# BSPD.net
KiCad netlist of a schematic drawn in Altium Designer
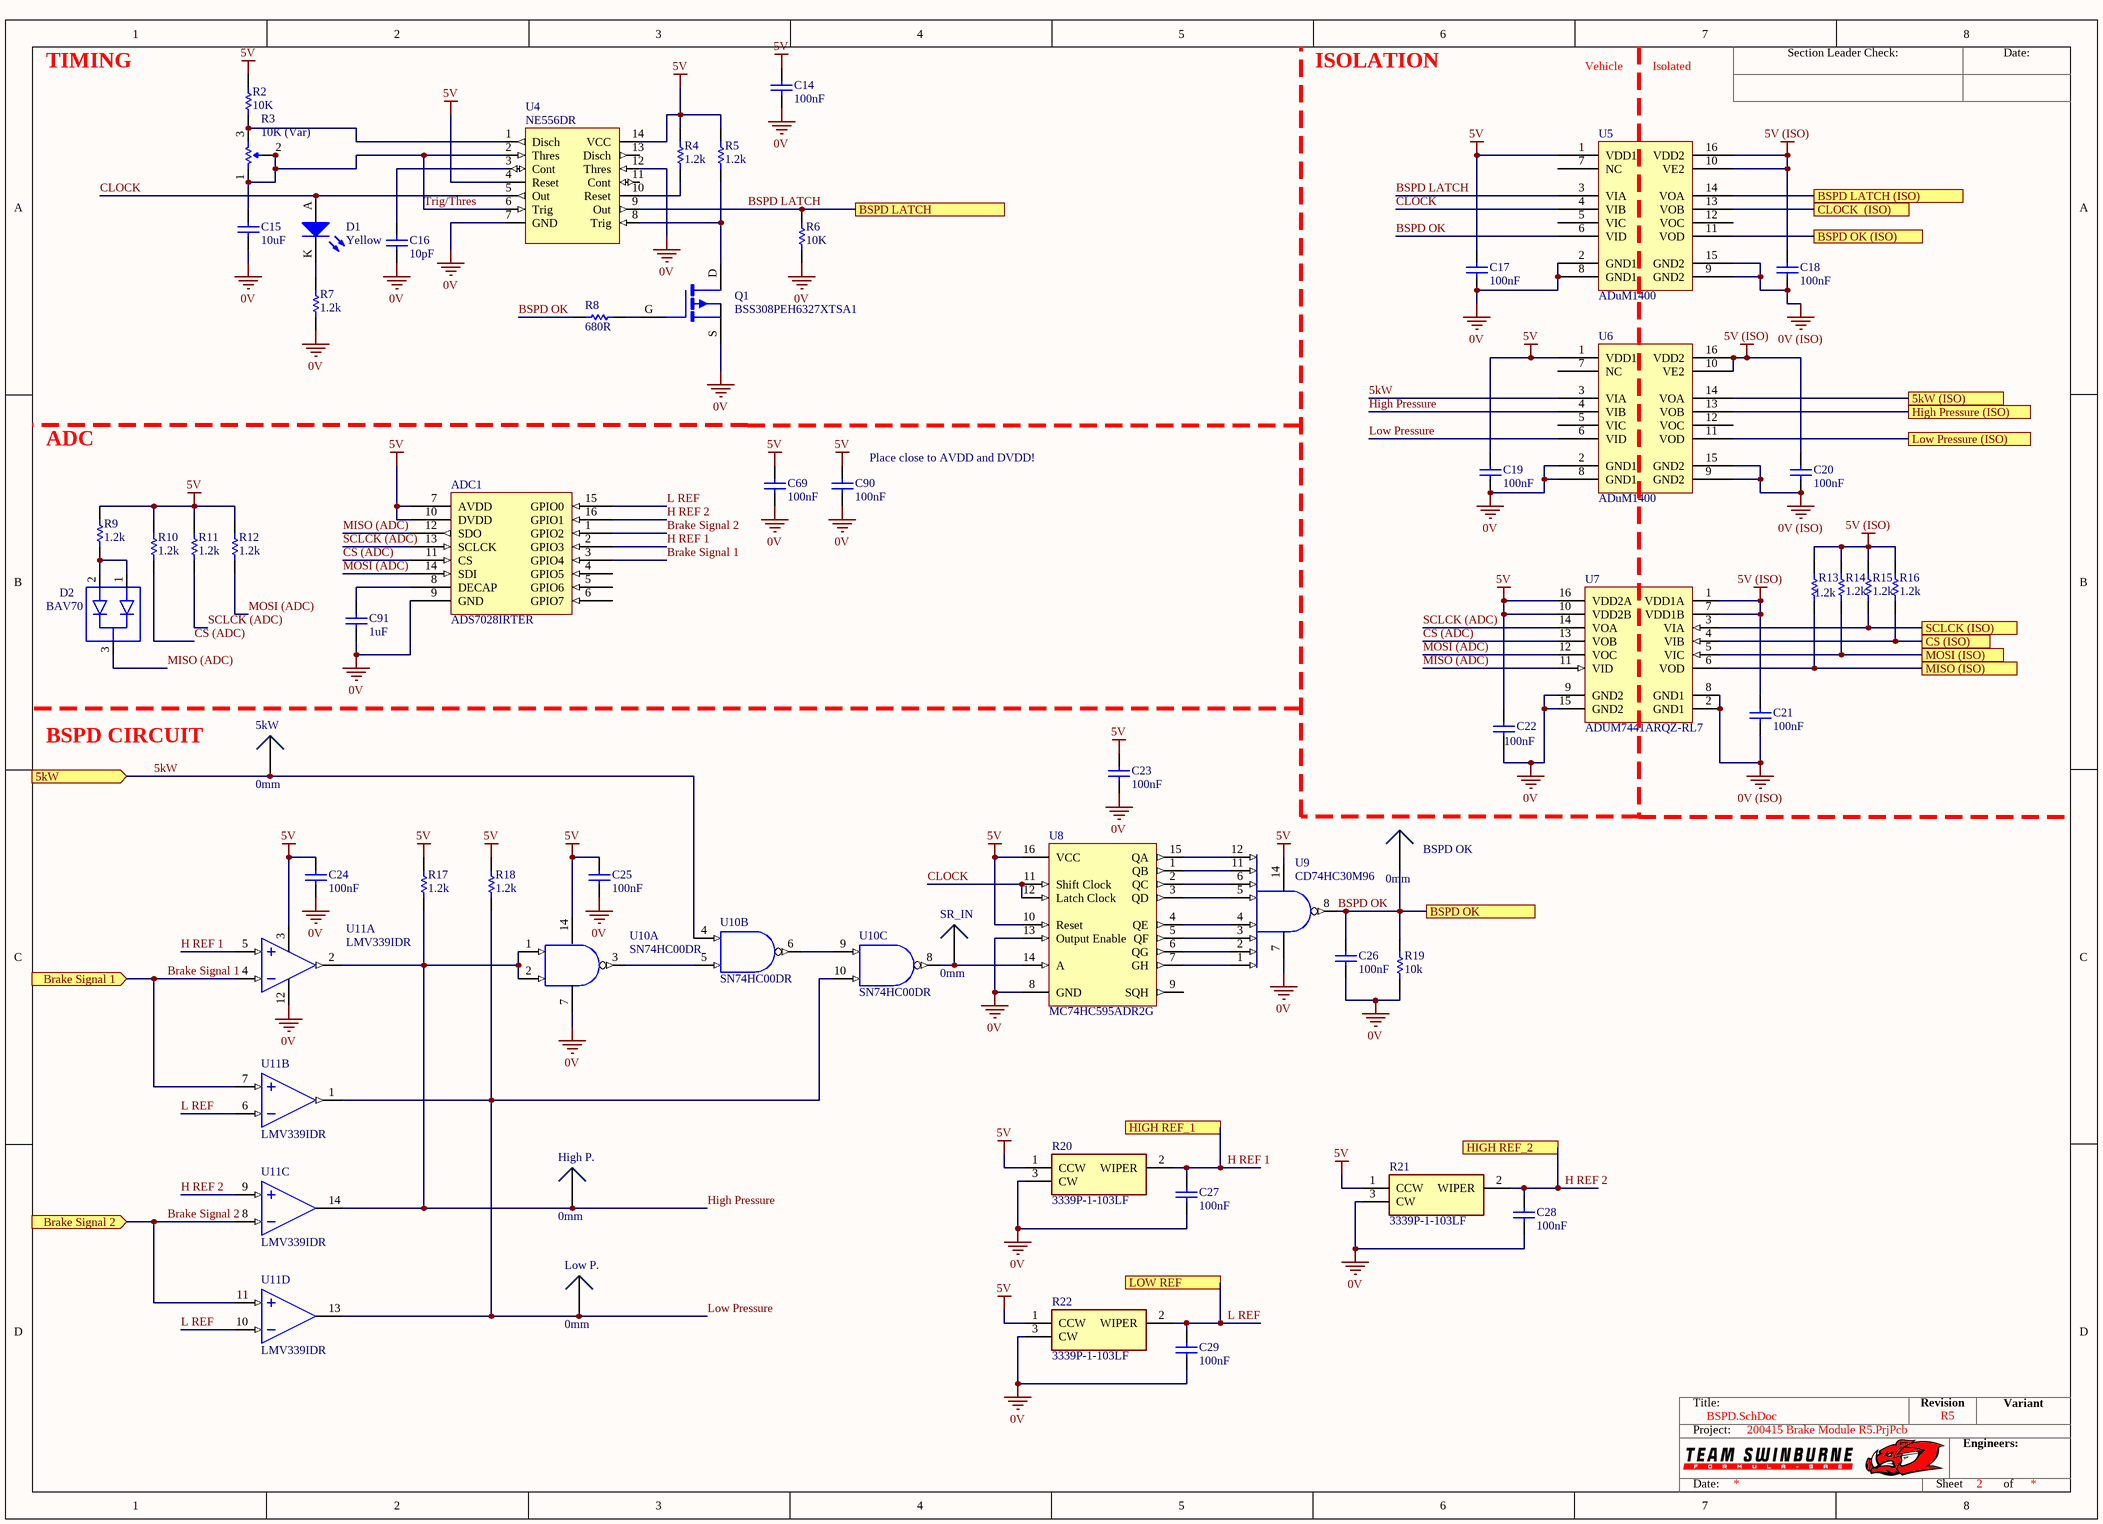
[diagram p0: BSPD.SchDoc]

(export (version "E")
  (design (tool "Eeschema 10.0.6"))
  (components
    (comp (ref "5kW")
      (value "0mm")
      (footprint "SMD Test Point")
      (fields (field (name "PART NUMBER") "SMD Test Point") (field (name "CONTACT") "NA"))
      (libsource (lib "ts_20-standard-connectors") (part "Test Point"))
    )
    (comp (ref "ADC1")
      (value "ADS7028IRTER")
      (footprint "WFQN-16")
      (description "IC ADC 12BIT SAR 16WQFN")
      (fields (field (name "MANUFACTURER") "Texas Instruments"))
      (libsource (lib "ts_standard_library") (part "ADS7028IRTER"))
    )
    (comp (ref "BSPD OK")
      (value "0mm")
      (footprint "SMD Test Point")
      (fields (field (name "PART NUMBER") "SMD Test Point") (field (name "CONTACT") "NA"))
      (libsource (lib "ts_20-standard-connectors") (part "Test Point"))
    )
    (comp (ref "C14")
      (value "100nF")
      (footprint "C0603")
      (fields (field (name "PART NUMBER") "CC0603ZPY5V9BB104") (field (name "TOLERANCE") "5%"))
      (libsource (lib "AMS_Component_Library") (part "Capacitor"))
    )
    (comp (ref "C15")
      (value "10uF")
      (footprint "C0603")
      (fields (field (name "PART NUMBER") "GRM188R6YA106MA73D") (field (name "TOLERANCE") "20%"))
      (libsource (lib "AMS_Component_Library") (part "Capacitor"))
    )
    (comp (ref "C16")
      (value "10pF")
      (footprint "C0603")
      (fields (field (name "PART NUMBER") "CC0603JPNPO9BN100") (field (name "TOLERANCE") "5%"))
      (libsource (lib "AMS_Component_Library") (part "Capacitor"))
    )
    (comp (ref "C17")
      (value "100nF")
      (footprint "C0603")
      (fields (field (name "PART NUMBER") "CC0603ZPY5V9BB104") (field (name "TOLERANCE") "5%"))
      (libsource (lib "AMS_Component_Library") (part "Capacitor"))
    )
    (comp (ref "C18")
      (value "100nF")
      (footprint "C0603")
      (fields (field (name "PART NUMBER") "CC0603ZPY5V9BB104") (field (name "TOLERANCE") "5%"))
      (libsource (lib "AMS_Component_Library") (part "Capacitor"))
    )
    (comp (ref "C19")
      (value "100nF")
      (footprint "C0603")
      (fields (field (name "PART NUMBER") "CC0603ZPY5V9BB104") (field (name "TOLERANCE") "5%"))
      (libsource (lib "AMS_Component_Library") (part "Capacitor"))
    )
    (comp (ref "C20")
      (value "100nF")
      (footprint "C0603")
      (fields (field (name "PART NUMBER") "CC0603ZPY5V9BB104") (field (name "TOLERANCE") "5%"))
      (libsource (lib "AMS_Component_Library") (part "Capacitor"))
    )
    (comp (ref "C21")
      (value "100nF")
      (footprint "C0603")
      (fields (field (name "PART NUMBER") "CC0603ZPY5V9BB104") (field (name "TOLERANCE") "5%"))
      (libsource (lib "AMS_Component_Library") (part "Capacitor"))
    )
    (comp (ref "C22")
      (value "100nF")
      (footprint "C0603")
      (fields (field (name "PART NUMBER") "CC0603ZPY5V9BB104") (field (name "TOLERANCE") "5%"))
      (libsource (lib "AMS_Component_Library") (part "Capacitor"))
    )
    (comp (ref "C23")
      (value "100nF")
      (footprint "C0603")
      (fields (field (name "PART NUMBER") "CC0603ZPY5V9BB104") (field (name "TOLERANCE") "5%"))
      (libsource (lib "AMS_Component_Library") (part "Capacitor"))
    )
    (comp (ref "C24")
      (value "100nF")
      (footprint "C0603")
      (fields (field (name "PART NUMBER") "CC0603ZPY5V9BB104") (field (name "TOLERANCE") "5%"))
      (libsource (lib "AMS_Component_Library") (part "Capacitor"))
    )
    (comp (ref "C25")
      (value "100nF")
      (footprint "C0603")
      (fields (field (name "PART NUMBER") "CC0603ZPY5V9BB104") (field (name "TOLERANCE") "5%"))
      (libsource (lib "AMS_Component_Library") (part "Capacitor"))
    )
    (comp (ref "C26")
      (value "100nF")
      (footprint "C0603")
      (fields (field (name "PART NUMBER") "CC0603ZPY5V9BB104") (field (name "TOLERANCE") "5%"))
      (libsource (lib "AMS_Component_Library") (part "Capacitor"))
    )
    (comp (ref "C27")
      (value "100nF")
      (footprint "0805")
      (fields
        (field (name "PART NUMBER") "GCM21BR71H104KA37L")
        (field (name "TOLERANCE") "±10%")
        (field (name "MANUFACTURER") "muRata")
      )
      (libsource (lib "ts_20-standard-library") (part "Capacitor"))
    )
    (comp (ref "C28")
      (value "100nF")
      (footprint "0805")
      (fields
        (field (name "PART NUMBER") "GCM21BR71H104KA37L")
        (field (name "TOLERANCE") "±10%")
        (field (name "MANUFACTURER") "muRata")
      )
      (libsource (lib "ts_20-standard-library") (part "Capacitor"))
    )
    (comp (ref "C29")
      (value "100nF")
      (footprint "0805")
      (fields
        (field (name "PART NUMBER") "GCM21BR71H104KA37L")
        (field (name "TOLERANCE") "±10%")
        (field (name "MANUFACTURER") "muRata")
      )
      (libsource (lib "ts_20-standard-library") (part "Capacitor"))
    )
    (comp (ref "C69")
      (value "100nF")
      (footprint "C0603")
      (fields (field (name "PART NUMBER") "CC0603ZPY5V9BB104") (field (name "TOLERANCE") "5%"))
      (libsource (lib "AMS_Component_Library") (part "Capacitor"))
    )
    (comp (ref "C90")
      (value "100nF")
      (footprint "C0603")
      (fields (field (name "PART NUMBER") "CC0603ZPY5V9BB104") (field (name "TOLERANCE") "5%"))
      (libsource (lib "AMS_Component_Library") (part "Capacitor"))
    )
    (comp (ref "C91")
      (value "1uF")
      (footprint "0603")
      (fields
        (field (name "PART NUMBER") "GRT188R61H105ME13D")
        (field (name "TOLERANCE") "20%")
        (field (name "MANUFACTURER") "muRata")
      )
      (libsource (lib "ts_20-standard-library") (part "Capacitor"))
    )
    (comp (ref "D1")
      (value "Yellow")
      (footprint "0805 LED")
      (description "Yellow LED Indication - Discrete 1.75V 0805 (2012 Metric)")
      (fields (field (name "PART NUMBER") "SML-211YTT86") (field (name "MANUFACTURER") "ROHM Semiconductor"))
      (libsource (lib "ts_20-standard-library") (part "LED"))
    )
    (comp (ref "D2")
      (value "BAV70")
      (footprint "BAV70-Footprint-1")
      (description "DIODE ARRAY GP 70V 200mA SOT23-3")
      (libsource (lib "Team Swinburne") (part "BAV70-Symbol-1"))
    )
    (comp (ref "High P.")
      (value "0mm")
      (footprint "SMD Test Point")
      (fields (field (name "PART NUMBER") "SMD Test Point") (field (name "CONTACT") "NA"))
      (libsource (lib "ts_20-standard-connectors") (part "Test Point"))
    )
    (comp (ref "Low P.")
      (value "0mm")
      (footprint "SMD Test Point")
      (fields (field (name "PART NUMBER") "SMD Test Point") (field (name "CONTACT") "NA"))
      (libsource (lib "ts_20-standard-connectors") (part "Test Point"))
    )
    (comp (ref "Q1")
      (value "BSS308PEH6327XTSA1")
      (footprint "IN SOT-23 MOSFET")
      (description "P-Channel 30V 2A (Ta) 500mW (Ta) Surface Mount SOT-23-3")
      (fields
        (field (name "MANUFACTURER") "Infineon Technologies")
        (field (name "DIGIKEY PART NUMBER") "BSS308PEH6327XTSA1CT-ND")
        (field (name "PUBLISHER") "Altium Limited")
      )
      (libsource (lib "ts_20-standard-library") (part "MOSFET-P"))
    )
    (comp (ref "R2")
      (value "10K")
      (footprint "R0603")
      (fields (field (name "PART NUMBER") "RA73F1J10KBTD") (field (name "TOLERANCE") "0.1%"))
      (libsource (lib "AMS_Component_Library") (part "Resistor"))
    )
    (comp (ref "R3")
      (value "10K (Var)")
      (footprint "B 3296")
      (fields
        (field (name "PART NUMBER") "3296W-1-103LF")
        (field (name "MANUFACTURER") "Bournes Inc")
        (field (name "TOLERANCE") "0.1")
      )
      (libsource (lib "ts_20-standard-library") (part "Resistor (Potentiometer)"))
    )
    (comp (ref "R4")
      (value "1.2k")
      (footprint "R0603")
      (fields (field (name "PART NUMBER") "ERJ-PA3J122V") (field (name "TOLERANCE") "1%"))
      (libsource (lib "AMS_Component_Library") (part "Resistor"))
    )
    (comp (ref "R5")
      (value "1.2k")
      (footprint "R0603")
      (fields (field (name "PART NUMBER") "ERJ-PA3J122V") (field (name "TOLERANCE") "1%"))
      (libsource (lib "AMS_Component_Library") (part "Resistor"))
    )
    (comp (ref "R6")
      (value "10K")
      (footprint "R0603")
      (fields (field (name "PART NUMBER") "RA73F1J10KBTD") (field (name "TOLERANCE") "0.1%"))
      (libsource (lib "AMS_Component_Library") (part "Resistor"))
    )
    (comp (ref "R7")
      (value "1.2k")
      (footprint "R0603")
      (fields (field (name "PART NUMBER") "ERJ-PA3J122V") (field (name "TOLERANCE") "1%"))
      (libsource (lib "AMS_Component_Library") (part "Resistor"))
    )
    (comp (ref "R8")
      (value "680R")
      (footprint "R0603")
      (fields (field (name "PART NUMBER") "RCP0603B680RGEA") (field (name "TOLERANCE") "2%"))
      (libsource (lib "AMS_Component_Library") (part "Resistor"))
    )
    (comp (ref "R9")
      (value "1.2k")
      (footprint "R0603")
      (fields (field (name "PART NUMBER") "ERJ-PA3J122V") (field (name "TOLERANCE") "1%"))
      (libsource (lib "AMS_Component_Library") (part "Resistor"))
    )
    (comp (ref "R10")
      (value "1.2k")
      (footprint "R0603")
      (fields (field (name "PART NUMBER") "ERJ-PA3J122V") (field (name "TOLERANCE") "1%"))
      (libsource (lib "AMS_Component_Library") (part "Resistor"))
    )
    (comp (ref "R11")
      (value "1.2k")
      (footprint "R0603")
      (fields (field (name "PART NUMBER") "ERJ-PA3J122V") (field (name "TOLERANCE") "1%"))
      (libsource (lib "AMS_Component_Library") (part "Resistor"))
    )
    (comp (ref "R12")
      (value "1.2k")
      (footprint "R0603")
      (fields (field (name "PART NUMBER") "ERJ-PA3J122V") (field (name "TOLERANCE") "1%"))
      (libsource (lib "AMS_Component_Library") (part "Resistor"))
    )
    (comp (ref "R13")
      (value "1.2k")
      (footprint "R0603")
      (fields (field (name "PART NUMBER") "ERJ-PA3J122V") (field (name "TOLERANCE") "1%"))
      (libsource (lib "AMS_Component_Library") (part "Resistor"))
    )
    (comp (ref "R14")
      (value "1.2k")
      (footprint "R0603")
      (fields (field (name "PART NUMBER") "ERJ-PA3J122V") (field (name "TOLERANCE") "1%"))
      (libsource (lib "AMS_Component_Library") (part "Resistor"))
    )
    (comp (ref "R15")
      (value "1.2k")
      (footprint "R0603")
      (fields (field (name "PART NUMBER") "ERJ-PA3J122V") (field (name "TOLERANCE") "1%"))
      (libsource (lib "AMS_Component_Library") (part "Resistor"))
    )
    (comp (ref "R16")
      (value "1.2k")
      (footprint "R0603")
      (fields (field (name "PART NUMBER") "ERJ-PA3J122V") (field (name "TOLERANCE") "1%"))
      (libsource (lib "AMS_Component_Library") (part "Resistor"))
    )
    (comp (ref "R17")
      (value "1.2k")
      (footprint "R0603")
      (fields (field (name "PART NUMBER") "ERJ-PA3J122V") (field (name "TOLERANCE") "1%"))
      (libsource (lib "AMS_Component_Library") (part "Resistor"))
    )
    (comp (ref "R18")
      (value "1.2k")
      (footprint "R0603")
      (fields (field (name "PART NUMBER") "ERJ-PA3J122V") (field (name "TOLERANCE") "1%"))
      (libsource (lib "AMS_Component_Library") (part "Resistor"))
    )
    (comp (ref "R19")
      (value "10k")
      (footprint "0805")
      (fields
        (field (name "PART NUMBER") "RC0805FR0710KL")
        (field (name "MANUFACTURER") "YAGEO")
        (field (name "TOLERANCE") "0.01")
      )
      (libsource (lib "ts_20-standard-library") (part "Resistor"))
    )
    (comp (ref "R20")
      (value "3339P-1-103LF")
      (footprint "SamacSys:3339P1103LF")
      (description "Variable Resistor")
      (fields (field (name "MOUSER PART NUMBER") "652-3339P-1-103LF"))
      (libsource (lib "*") (part "3339P-1-103LF"))
    )
    (comp (ref "R21")
      (value "3339P-1-103LF")
      (footprint "SamacSys:3339P1103LF")
      (description "Variable Resistor")
      (fields (field (name "MOUSER PART NUMBER") "652-3339P-1-103LF"))
      (libsource (lib "*") (part "3339P-1-103LF"))
    )
    (comp (ref "R22")
      (value "3339P-1-103LF")
      (footprint "SamacSys:3339P1103LF")
      (description "Variable Resistor")
      (fields (field (name "MOUSER PART NUMBER") "652-3339P-1-103LF"))
      (libsource (lib "*") (part "3339P-1-103LF"))
    )
    (comp (ref "SR_IN")
      (value "0mm")
      (footprint "SMD Test Point")
      (fields (field (name "PART NUMBER") "SMD Test Point") (field (name "CONTACT") "NA"))
      (libsource (lib "ts_20-standard-connectors") (part "Test Point"))
    )
    (comp (ref "U4")
      (value "NE556DR")
      (footprint "14 SOIC")
      (description "IC OSC TIMER DUAL 100KHZ 14SOIC")
      (fields
        (field (name "MANUFACTURER") "Texas Instruments")
        (field (name "DIGIKEY PART NUMBER") "296-26240-1-ND")
      )
      (libsource (lib "ts_20-standard-library") (part "NE556DR"))
    )
    (comp (ref "U5")
      (value "ADuM1400")
      (footprint "SOIC16-W")
      (description "DIGITAL ISOLATOR, QUAD CHANNEL")
      (libsource (lib "AMS_Component_Library") (part "ADuM1400"))
    )
    (comp (ref "U6")
      (value "ADuM1400")
      (footprint "SOIC16-W")
      (description "DIGITAL ISOLATOR, QUAD CHANNEL")
      (libsource (lib "AMS_Component_Library") (part "ADuM1400"))
    )
    (comp (ref "U7")
      (value "ADUM7441ARQZ-RL7")
      (footprint "ADI-RQ-16_M")
      (description "Digital Isolator CMOS 4-CH 1Mbps 16-Pin QSOP T/R")
      (libsource (lib "Team Swinburne") (part "ADI-ADUM7441-RQ-16"))
    )
    (comp (ref "U8")
      (value "MC74HC595ADR2G")
      (footprint "ON 16-SOIC")
      (description "IC SHIFT REGISTR 8BIT 3ST 16SOIC")
      (fields
        (field (name "MANUFACTURER") "ON Semiconductor")
        (field (name "DIGIKEY PART NUMBER") "MC74HC595ADR2GOSCT-ND")
      )
      (libsource (lib "ts_20-standard-library") (part "MC74HC595ADR2G"))
    )
    (comp (ref "U9")
      (value "CD74HC30M96")
      (footprint "TI 14-SOIC")
      (description "IC GATE NAND 1CH 8-INP 14SOIC")
      (fields
        (field (name "MANUFACTURER") "Texas Instruments")
        (field (name "DIGIKEY PART NUMBER") "296-14521-1-ND")
      )
      (libsource (lib "ts_20-standard-library") (part "CD74HC30M96"))
    )
    (comp (ref "U10")
      (value "SN74HC00DR")
      (footprint "TI 14-SOIC")
      (description "NAND Gate IC 4 Channel 14-SOIC")
      (fields
        (field (name "MANUFACTURER") "Texas Instruments")
        (field (name "DIGIKEY PART NUMBER") "296-1187-2-ND")
      )
      (libsource (lib "ts_20-standard-library") (part "SN74HC00DR"))
    )
    (comp (ref "U11")
      (value "LMV339IDR")
      (footprint "TI 14-SOIC")
      (description "Comparator General Purpose Open Collector 14-SOIC")
      (fields
        (field (name "MANUFACTURER") "Texas Instruments")
        (field (name "DIGIKEY PART NUMBER") "296-6611-2-ND")
      )
      (libsource (lib "ts_20-standard-library") (part "LMV339IDR"))
    )
  )
  (nets
    (net (code "1") (name "/5kW") (class "Default")
      (node (ref "5kW") (pin "1") (pinfunction "1_1") (pintype "passive"))
      (node (ref "U10") (pin "4") (pinfunction "2A_4") (pintype "input"))
      (node (ref "U6") (pin "3") (pinfunction "VIA_3") (pintype "passive"))
    )
    (net (code "2") (name "/5kW (ISO)") (class "Default")
      (node (ref "U6") (pin "14") (pinfunction "VOA_14") (pintype "passive"))
    )
    (net (code "3") (name "/BSPD LATCH") (class "Default")
      (node (ref "R6") (pin "2") (pinfunction "2_2") (pintype "passive"))
      (node (ref "U4") (pin "9") (pinfunction "Out_9") (pintype "output"))
      (node (ref "U5") (pin "3") (pinfunction "VIA_3") (pintype "passive"))
    )
    (net (code "4") (name "/BSPD LATCH (ISO)") (class "Default")
      (node (ref "U5") (pin "14") (pinfunction "VOA_14") (pintype "passive"))
    )
    (net (code "5") (name "/BSPD OK") (class "Default")
      (node (ref "BSPD OK") (pin "1") (pinfunction "1_1") (pintype "passive"))
      (node (ref "C26") (pin "2") (pinfunction "2_2") (pintype "passive"))
      (node (ref "R19") (pin "2") (pinfunction "2_2") (pintype "passive"))
      (node (ref "R8") (pin "1") (pinfunction "1_1") (pintype "passive"))
      (node (ref "U5") (pin "6") (pinfunction "VID_6") (pintype "passive"))
      (node (ref "U9") (pin "8") (pinfunction "Output_8") (pintype "output"))
    )
    (net (code "6") (name "/BSPD OK (ISO)") (class "Default")
      (node (ref "U5") (pin "11") (pinfunction "VOD_11") (pintype "passive"))
    )
    (net (code "7") (name "/Brake Signal 1") (class "Default")
      (node (ref "ADC1") (pin "3") (pinfunction "GPIO4_3") (pintype "input"))
      (node (ref "U11") (pin "4") (pinfunction "IN_A-_4") (pintype "input"))
      (node (ref "U11") (pin "7") (pinfunction "IN_B+_7") (pintype "input"))
    )
    (net (code "8") (name "/Brake Signal 2") (class "Default")
      (node (ref "ADC1") (pin "1") (pinfunction "GPIO2_1") (pintype "input"))
      (node (ref "U11") (pin "11") (pinfunction "IN_D+_11") (pintype "input"))
      (node (ref "U11") (pin "8") (pinfunction "IN_C-_8") (pintype "input"))
    )
    (net (code "9") (name "/CLOCK") (class "Default")
      (node (ref "D1") (pin "A") (pinfunction "A_A") (pintype "passive"))
      (node (ref "U4") (pin "5") (pinfunction "Out_5") (pintype "output"))
      (node (ref "U5") (pin "4") (pinfunction "VIB_4") (pintype "passive"))
      (node (ref "U8") (pin "11") (pinfunction "Shift_Clock_11") (pintype "input"))
      (node (ref "U8") (pin "12") (pinfunction "Latch_Clock_12") (pintype "input"))
    )
    (net (code "10") (name "/CLOCK  (ISO)") (class "Default")
      (node (ref "U5") (pin "13") (pinfunction "VOB_13") (pintype "passive"))
    )
    (net (code "11") (name "/CS (ADC)") (class "Default")
      (node (ref "ADC1") (pin "11") (pinfunction "CS_11") (pintype "input"))
      (node (ref "R10") (pin "1") (pinfunction "1_1") (pintype "passive"))
      (node (ref "U7") (pin "13") (pinfunction "VOB_13") (pintype "tri_state"))
    )
    (net (code "12") (name "/CS (ISO)") (class "Default")
      (node (ref "R16") (pin "1") (pinfunction "1_1") (pintype "passive"))
      (node (ref "U7") (pin "4") (pinfunction "VIB_4") (pintype "input"))
    )
    (net (code "13") (name "/H REF 1") (class "Default")
      (node (ref "ADC1") (pin "2") (pinfunction "GPIO3_2") (pintype "input"))
      (node (ref "C27") (pin "2") (pinfunction "2_2") (pintype "passive"))
      (node (ref "R20") (pin "2") (pinfunction "WIPER_2") (pintype "passive"))
      (node (ref "U11") (pin "5") (pinfunction "IN_A+_5") (pintype "input"))
    )
    (net (code "14") (name "/H REF 2") (class "Default")
      (node (ref "ADC1") (pin "16") (pinfunction "GPIO1_16") (pintype "input"))
      (node (ref "C28") (pin "2") (pinfunction "2_2") (pintype "passive"))
      (node (ref "R21") (pin "2") (pinfunction "WIPER_2") (pintype "passive"))
      (node (ref "U11") (pin "9") (pinfunction "IN_C+_9") (pintype "input"))
    )
    (net (code "15") (name "/High Pressure") (class "Default")
      (node (ref "High P.") (pin "1") (pinfunction "1_1") (pintype "passive"))
      (node (ref "R17") (pin "1") (pinfunction "1_1") (pintype "passive"))
      (node (ref "U10") (pin "1") (pinfunction "1A_1") (pintype "input"))
      (node (ref "U10") (pin "2") (pinfunction "1B_2") (pintype "input"))
      (node (ref "U11") (pin "14") (pinfunction "OUT_C_14") (pintype "passive"))
      (node (ref "U11") (pin "2") (pinfunction "OUT_A_2") (pintype "output"))
      (node (ref "U6") (pin "4") (pinfunction "VIB_4") (pintype "passive"))
    )
    (net (code "16") (name "/High Pressure (ISO)") (class "Default")
      (node (ref "U6") (pin "13") (pinfunction "VOB_13") (pintype "passive"))
    )
    (net (code "17") (name "/L REF") (class "Default")
      (node (ref "ADC1") (pin "15") (pinfunction "GPIO0_15") (pintype "input"))
      (node (ref "C29") (pin "2") (pinfunction "2_2") (pintype "passive"))
      (node (ref "R22") (pin "2") (pinfunction "WIPER_2") (pintype "passive"))
      (node (ref "U11") (pin "10") (pinfunction "IN_D-_10") (pintype "input"))
      (node (ref "U11") (pin "6") (pinfunction "IN_B-_6") (pintype "input"))
    )
    (net (code "18") (name "/Low Pressure") (class "Default")
      (node (ref "Low P.") (pin "1") (pinfunction "1_1") (pintype "passive"))
      (node (ref "R18") (pin "1") (pinfunction "1_1") (pintype "passive"))
      (node (ref "U10") (pin "10") (pinfunction "3B_10") (pintype "input"))
      (node (ref "U11") (pin "1") (pinfunction "OUT_B_1") (pintype "output"))
      (node (ref "U11") (pin "13") (pinfunction "OUT_D_13") (pintype "passive"))
      (node (ref "U6") (pin "6") (pinfunction "VID_6") (pintype "passive"))
    )
    (net (code "19") (name "/Low Pressure (ISO)") (class "Default")
      (node (ref "U6") (pin "11") (pinfunction "VOD_11") (pintype "passive"))
    )
    (net (code "20") (name "/MISO (ADC)") (class "Default")
      (node (ref "ADC1") (pin "12") (pinfunction "SDO_12") (pintype "output"))
      (node (ref "D2") (pin "3") (pinfunction "CC_3") (pintype "passive"))
      (node (ref "U7") (pin "11") (pinfunction "VID_11") (pintype "input"))
    )
    (net (code "21") (name "/MISO (ISO)") (class "Default")
      (node (ref "R13") (pin "1") (pinfunction "1_1") (pintype "passive"))
      (node (ref "U7") (pin "6") (pinfunction "VOD_6") (pintype "tri_state"))
    )
    (net (code "22") (name "/MOSI (ADC)") (class "Default")
      (node (ref "ADC1") (pin "14") (pinfunction "SDI_14") (pintype "input"))
      (node (ref "R12") (pin "1") (pinfunction "1_1") (pintype "passive"))
      (node (ref "U7") (pin "12") (pinfunction "VOC_12") (pintype "tri_state"))
    )
    (net (code "23") (name "/MOSI (ISO)") (class "Default")
      (node (ref "R14") (pin "1") (pinfunction "1_1") (pintype "passive"))
      (node (ref "U7") (pin "5") (pinfunction "VIC_5") (pintype "input"))
    )
    (net (code "24") (name "/SCLCK (ADC)") (class "Default")
      (node (ref "ADC1") (pin "13") (pinfunction "SCLCK_13") (pintype "input"))
      (node (ref "R11") (pin "1") (pinfunction "1_1") (pintype "passive"))
      (node (ref "U7") (pin "14") (pinfunction "VOA_14") (pintype "tri_state"))
    )
    (net (code "25") (name "/SCLCK (ISO)") (class "Default")
      (node (ref "R15") (pin "1") (pinfunction "1_1") (pintype "passive"))
      (node (ref "U7") (pin "3") (pinfunction "VIA_3") (pintype "input"))
    )
    (net (code "26") (name "/Trig{slash}Thres") (class "Default")
      (node (ref "C15") (pin "2") (pinfunction "2_2") (pintype "passive"))
      (node (ref "R3") (pin "1") (pinfunction "CCW_1") (pintype "passive"))
      (node (ref "R3") (pin "2") (pinfunction "Wiper_2") (pintype "passive"))
      (node (ref "U4") (pin "2") (pinfunction "Thres_2") (pintype "input"))
      (node (ref "U4") (pin "6") (pinfunction "Trig_6") (pintype "input"))
    )
    (net (code "27") (name "0V") (class "Default")
      (node (ref "ADC1") (pin "9") (pinfunction "GND_9") (pintype "power_in"))
      (node (ref "C14") (pin "1") (pinfunction "1_1") (pintype "passive"))
      (node (ref "C15") (pin "1") (pinfunction "1_1") (pintype "passive"))
      (node (ref "C16") (pin "1") (pinfunction "1_1") (pintype "passive"))
      (node (ref "C17") (pin "1") (pinfunction "1_1") (pintype "passive"))
      (node (ref "C19") (pin "1") (pinfunction "1_1") (pintype "passive"))
      (node (ref "C22") (pin "1") (pinfunction "1_1") (pintype "passive"))
      (node (ref "C23") (pin "1") (pinfunction "1_1") (pintype "passive"))
      (node (ref "C24") (pin "1") (pinfunction "1_1") (pintype "passive"))
      (node (ref "C25") (pin "1") (pinfunction "1_1") (pintype "passive"))
      (node (ref "C26") (pin "1") (pinfunction "1_1") (pintype "passive"))
      (node (ref "C27") (pin "1") (pinfunction "1_1") (pintype "passive"))
      (node (ref "C28") (pin "1") (pinfunction "1_1") (pintype "passive"))
      (node (ref "C29") (pin "1") (pinfunction "1_1") (pintype "passive"))
      (node (ref "C69") (pin "1") (pinfunction "1_1") (pintype "passive"))
      (node (ref "C90") (pin "1") (pinfunction "1_1") (pintype "passive"))
      (node (ref "C91") (pin "1") (pinfunction "1_1") (pintype "passive"))
      (node (ref "Q1") (pin "S") (pinfunction "S_S") (pintype "passive"))
      (node (ref "R19") (pin "1") (pinfunction "1_1") (pintype "passive"))
      (node (ref "R20") (pin "3") (pinfunction "CW_3") (pintype "passive"))
      (node (ref "R21") (pin "3") (pinfunction "CW_3") (pintype "passive"))
      (node (ref "R22") (pin "3") (pinfunction "CW_3") (pintype "passive"))
      (node (ref "R6") (pin "1") (pinfunction "1_1") (pintype "passive"))
      (node (ref "R7") (pin "1") (pinfunction "1_1") (pintype "passive"))
      (node (ref "U10") (pin "7") (pinfunction "GND_7") (pintype "power_in"))
      (node (ref "U11") (pin "12") (pinfunction "V-_12") (pintype "power_in"))
      (node (ref "U4") (pin "12") (pinfunction "Thres_12") (pintype "input"))
      (node (ref "U4") (pin "7") (pinfunction "GND_7") (pintype "power_in"))
      (node (ref "U5") (pin "2") (pinfunction "GND1_2") (pintype "passive"))
      (node (ref "U5") (pin "8") (pinfunction "GND1_8") (pintype "passive"))
      (node (ref "U6") (pin "2") (pinfunction "GND1_2") (pintype "passive"))
      (node (ref "U6") (pin "8") (pinfunction "GND1_8") (pintype "passive"))
      (node (ref "U7") (pin "15") (pinfunction "GND2_15") (pintype "power_in"))
      (node (ref "U7") (pin "9") (pinfunction "GND2_9") (pintype "power_in"))
      (node (ref "U8") (pin "13") (pinfunction "Output_Enable_13") (pintype "input"))
      (node (ref "U8") (pin "8") (pinfunction "GND_8") (pintype "power_in"))
      (node (ref "U9") (pin "7") (pinfunction "GND_7") (pintype "power_in"))
    )
    (net (code "28") (name "0V (ISO)") (class "Default")
      (node (ref "C18") (pin "1") (pinfunction "1_1") (pintype "passive"))
      (node (ref "C20") (pin "1") (pinfunction "1_1") (pintype "passive"))
      (node (ref "C21") (pin "1") (pinfunction "1_1") (pintype "passive"))
      (node (ref "U5") (pin "15") (pinfunction "GND2_15") (pintype "passive"))
      (node (ref "U5") (pin "9") (pinfunction "GND2_9") (pintype "passive"))
      (node (ref "U6") (pin "15") (pinfunction "GND2_15") (pintype "passive"))
      (node (ref "U6") (pin "9") (pinfunction "GND2_9") (pintype "passive"))
      (node (ref "U7") (pin "2") (pinfunction "GND1_2") (pintype "power_in"))
      (node (ref "U7") (pin "8") (pinfunction "GND1_8") (pintype "power_in"))
    )
    (net (code "29") (name "5V") (class "Default")
      (node (ref "ADC1") (pin "10") (pinfunction "DVDD_10") (pintype "power_in"))
      (node (ref "ADC1") (pin "7") (pinfunction "AVDD_7") (pintype "power_in"))
      (node (ref "C14") (pin "2") (pinfunction "2_2") (pintype "passive"))
      (node (ref "C17") (pin "2") (pinfunction "2_2") (pintype "passive"))
      (node (ref "C19") (pin "2") (pinfunction "2_2") (pintype "passive"))
      (node (ref "C22") (pin "2") (pinfunction "2_2") (pintype "passive"))
      (node (ref "C23") (pin "2") (pinfunction "2_2") (pintype "passive"))
      (node (ref "C24") (pin "2") (pinfunction "2_2") (pintype "passive"))
      (node (ref "C25") (pin "2") (pinfunction "2_2") (pintype "passive"))
      (node (ref "C69") (pin "2") (pinfunction "2_2") (pintype "passive"))
      (node (ref "C90") (pin "2") (pinfunction "2_2") (pintype "passive"))
      (node (ref "R10") (pin "2") (pinfunction "2_2") (pintype "passive"))
      (node (ref "R11") (pin "2") (pinfunction "2_2") (pintype "passive"))
      (node (ref "R12") (pin "2") (pinfunction "2_2") (pintype "passive"))
      (node (ref "R17") (pin "2") (pinfunction "2_2") (pintype "passive"))
      (node (ref "R18") (pin "2") (pinfunction "2_2") (pintype "passive"))
      (node (ref "R2") (pin "2") (pinfunction "2_2") (pintype "passive"))
      (node (ref "R20") (pin "1") (pinfunction "CCW_1") (pintype "passive"))
      (node (ref "R21") (pin "1") (pinfunction "CCW_1") (pintype "passive"))
      (node (ref "R22") (pin "1") (pinfunction "CCW_1") (pintype "passive"))
      (node (ref "R4") (pin "2") (pinfunction "2_2") (pintype "passive"))
      (node (ref "R5") (pin "2") (pinfunction "2_2") (pintype "passive"))
      (node (ref "R9") (pin "2") (pinfunction "2_2") (pintype "passive"))
      (node (ref "U10") (pin "14") (pinfunction "VCC_14") (pintype "power_in"))
      (node (ref "U11") (pin "3") (pinfunction "V+_3") (pintype "power_in"))
      (node (ref "U4") (pin "14") (pinfunction "VCC_14") (pintype "passive"))
      (node (ref "U4") (pin "4") (pinfunction "Reset_4") (pintype "passive"))
      (node (ref "U5") (pin "1") (pinfunction "VDD1_1") (pintype "passive"))
      (node (ref "U6") (pin "1") (pinfunction "VDD1_1") (pintype "passive"))
      (node (ref "U7") (pin "10") (pinfunction "VDD2B_10") (pintype "power_in"))
      (node (ref "U7") (pin "16") (pinfunction "VDD2A_16") (pintype "power_in"))
      (node (ref "U8") (pin "10") (pinfunction "Reset_10") (pintype "input"))
      (node (ref "U8") (pin "16") (pinfunction "VCC_16") (pintype "power_in"))
      (node (ref "U9") (pin "14") (pinfunction "VCC_14") (pintype "power_in"))
    )
    (net (code "30") (name "5V (ISO)") (class "Default")
      (node (ref "C18") (pin "2") (pinfunction "2_2") (pintype "passive"))
      (node (ref "C20") (pin "2") (pinfunction "2_2") (pintype "passive"))
      (node (ref "C21") (pin "2") (pinfunction "2_2") (pintype "passive"))
      (node (ref "R13") (pin "2") (pinfunction "2_2") (pintype "passive"))
      (node (ref "R14") (pin "2") (pinfunction "2_2") (pintype "passive"))
      (node (ref "R15") (pin "2") (pinfunction "2_2") (pintype "passive"))
      (node (ref "R16") (pin "2") (pinfunction "2_2") (pintype "passive"))
      (node (ref "U5") (pin "10") (pinfunction "VE2_10") (pintype "passive"))
      (node (ref "U5") (pin "16") (pinfunction "VDD2_16") (pintype "passive"))
      (node (ref "U6") (pin "10") (pinfunction "VE2_10") (pintype "passive"))
      (node (ref "U6") (pin "16") (pinfunction "VDD2_16") (pintype "passive"))
      (node (ref "U7") (pin "1") (pinfunction "VDD1A_1") (pintype "power_in"))
      (node (ref "U7") (pin "7") (pinfunction "VDD1B_7") (pintype "power_in"))
    )
    (net (code "31") (name "Net-(ADC1-DECAP)") (class "Default")
      (node (ref "ADC1") (pin "8") (pinfunction "DECAP_8") (pintype "power_in"))
      (node (ref "C91") (pin "2") (pinfunction "2_2") (pintype "passive"))
    )
    (net (code "32") (name "Net-(C16-Pad2)") (class "Default")
      (node (ref "C16") (pin "2") (pinfunction "2_2") (pintype "passive"))
      (node (ref "U4") (pin "3") (pinfunction "Cont_3") (pintype "bidirectional"))
    )
    (net (code "33") (name "Net-(D1-PadK)") (class "Default")
      (node (ref "D1") (pin "K") (pinfunction "K_K") (pintype "passive"))
      (node (ref "R7") (pin "2") (pinfunction "2_2") (pintype "passive"))
    )
    (net (code "34") (name "Net-(D2-A1)") (class "Default")
      (node (ref "D2") (pin "1") (pinfunction "A1_1") (pintype "passive"))
      (node (ref "D2") (pin "2") (pinfunction "A2_2") (pintype "passive"))
      (node (ref "R9") (pin "1") (pinfunction "1_1") (pintype "passive"))
    )
    (net (code "35") (name "Net-(Q1-PadD)") (class "Default")
      (node (ref "Q1") (pin "D") (pinfunction "D_D") (pintype "passive"))
      (node (ref "R5") (pin "1") (pinfunction "1_1") (pintype "passive"))
      (node (ref "U4") (pin "8") (pinfunction "Trig_8") (pintype "input"))
    )
    (net (code "36") (name "Net-(Q1-PadG)") (class "Default")
      (node (ref "Q1") (pin "G") (pinfunction "G_G") (pintype "passive"))
      (node (ref "R8") (pin "2") (pinfunction "2_2") (pintype "passive"))
    )
    (net (code "37") (name "Net-(R3-CW)") (class "Default")
      (node (ref "R2") (pin "1") (pinfunction "1_1") (pintype "passive"))
      (node (ref "R3") (pin "3") (pinfunction "CW_3") (pintype "passive"))
      (node (ref "U4") (pin "1") (pinfunction "Disch_1") (pintype "output"))
    )
    (net (code "38") (name "Net-(R4-Pad1)") (class "Default")
      (node (ref "R4") (pin "1") (pinfunction "1_1") (pintype "passive"))
      (node (ref "U4") (pin "10") (pinfunction "Reset_10") (pintype "passive"))
    )
    (net (code "39") (name "Net-(U8-GH)") (class "Default")
      (node (ref "U8") (pin "7") (pinfunction "GH_7") (pintype "output"))
      (node (ref "U9") (pin "1") (pinfunction "Input_1") (pintype "input"))
    )
    (net (code "40") (name "Net-(U8-QA)") (class "Default")
      (node (ref "U8") (pin "15") (pinfunction "QA_15") (pintype "output"))
      (node (ref "U9") (pin "12") (pinfunction "Input_12") (pintype "input"))
    )
    (net (code "41") (name "Net-(U8-QB)") (class "Default")
      (node (ref "U8") (pin "1") (pinfunction "QB_1") (pintype "output"))
      (node (ref "U9") (pin "11") (pinfunction "Input_11") (pintype "input"))
    )
    (net (code "42") (name "Net-(U8-QC)") (class "Default")
      (node (ref "U8") (pin "2") (pinfunction "QC_2") (pintype "output"))
      (node (ref "U9") (pin "6") (pinfunction "Input_6") (pintype "input"))
    )
    (net (code "43") (name "Net-(U8-QD)") (class "Default")
      (node (ref "U8") (pin "3") (pinfunction "QD_3") (pintype "output"))
      (node (ref "U9") (pin "5") (pinfunction "Input_5") (pintype "input"))
    )
    (net (code "44") (name "Net-(U8-QE)") (class "Default")
      (node (ref "U8") (pin "4") (pinfunction "QE_4") (pintype "output"))
      (node (ref "U9") (pin "4") (pinfunction "Input_4") (pintype "input"))
    )
    (net (code "45") (name "Net-(U8-QF)") (class "Default")
      (node (ref "U8") (pin "5") (pinfunction "QF_5") (pintype "output"))
      (node (ref "U9") (pin "3") (pinfunction "Input_3") (pintype "input"))
    )
    (net (code "46") (name "Net-(U8-QG)") (class "Default")
      (node (ref "U8") (pin "6") (pinfunction "QG_6") (pintype "output"))
      (node (ref "U9") (pin "2") (pinfunction "Input_2") (pintype "input"))
    )
    (net (code "47") (name "Net-(U10A-1Y)") (class "Default")
      (node (ref "U10") (pin "3") (pinfunction "1Y_3") (pintype "output"))
      (node (ref "U10") (pin "5") (pinfunction "2B_5") (pintype "input"))
    )
    (net (code "48") (name "Net-(U10B-2Y)") (class "Default")
      (node (ref "U10") (pin "6") (pinfunction "2Y_6") (pintype "output"))
      (node (ref "U10") (pin "9") (pinfunction "3A_9") (pintype "input"))
    )
    (net (code "49") (name "Net-(U10C-3Y)") (class "Default")
      (node (ref "SR_IN") (pin "1") (pinfunction "1_1") (pintype "passive"))
      (node (ref "U10") (pin "8") (pinfunction "3Y_8") (pintype "output"))
      (node (ref "U8") (pin "14") (pinfunction "A_14") (pintype "input"))
    )
    (net (code "50") (name "unconnected-(ADC1-GPIO5-Pad4)") (class "Default")
      (node (ref "ADC1") (pin "4") (pinfunction "GPIO5_4") (pintype "input"))
    )
    (net (code "51") (name "unconnected-(ADC1-GPIO6-Pad5)") (class "Default")
      (node (ref "ADC1") (pin "5") (pinfunction "GPIO6_5") (pintype "input"))
    )
    (net (code "52") (name "unconnected-(ADC1-GPIO7-Pad6)") (class "Default")
      (node (ref "ADC1") (pin "6") (pinfunction "GPIO7_6") (pintype "input"))
    )
    (net (code "53") (name "unconnected-(U4-Cont-Pad11)") (class "Default")
      (node (ref "U4") (pin "11") (pinfunction "Cont_11") (pintype "bidirectional"))
    )
    (net (code "54") (name "unconnected-(U4-Disch-Pad13)") (class "Default")
      (node (ref "U4") (pin "13") (pinfunction "Disch_13") (pintype "output"))
    )
    (net (code "55") (name "unconnected-(U5-NC-Pad7)") (class "Default")
      (node (ref "U5") (pin "7") (pinfunction "NC_7") (pintype "passive"))
    )
    (net (code "56") (name "unconnected-(U5-VIC-Pad5)") (class "Default")
      (node (ref "U5") (pin "5") (pinfunction "VIC_5") (pintype "passive"))
    )
    (net (code "57") (name "unconnected-(U5-VOC-Pad12)") (class "Default")
      (node (ref "U5") (pin "12") (pinfunction "VOC_12") (pintype "passive"))
    )
    (net (code "58") (name "unconnected-(U6-NC-Pad7)") (class "Default")
      (node (ref "U6") (pin "7") (pinfunction "NC_7") (pintype "passive"))
    )
    (net (code "59") (name "unconnected-(U6-VIC-Pad5)") (class "Default")
      (node (ref "U6") (pin "5") (pinfunction "VIC_5") (pintype "passive"))
    )
    (net (code "60") (name "unconnected-(U6-VOC-Pad12)") (class "Default")
      (node (ref "U6") (pin "12") (pinfunction "VOC_12") (pintype "passive"))
    )
    (net (code "61") (name "unconnected-(U8-SQH-Pad9)") (class "Default")
      (node (ref "U8") (pin "9") (pinfunction "SQH_9") (pintype "output"))
    )
  )
)
